# ra8875_40pin_REV-D.net
KiCad netlist of a schematic drawn in EAGLE
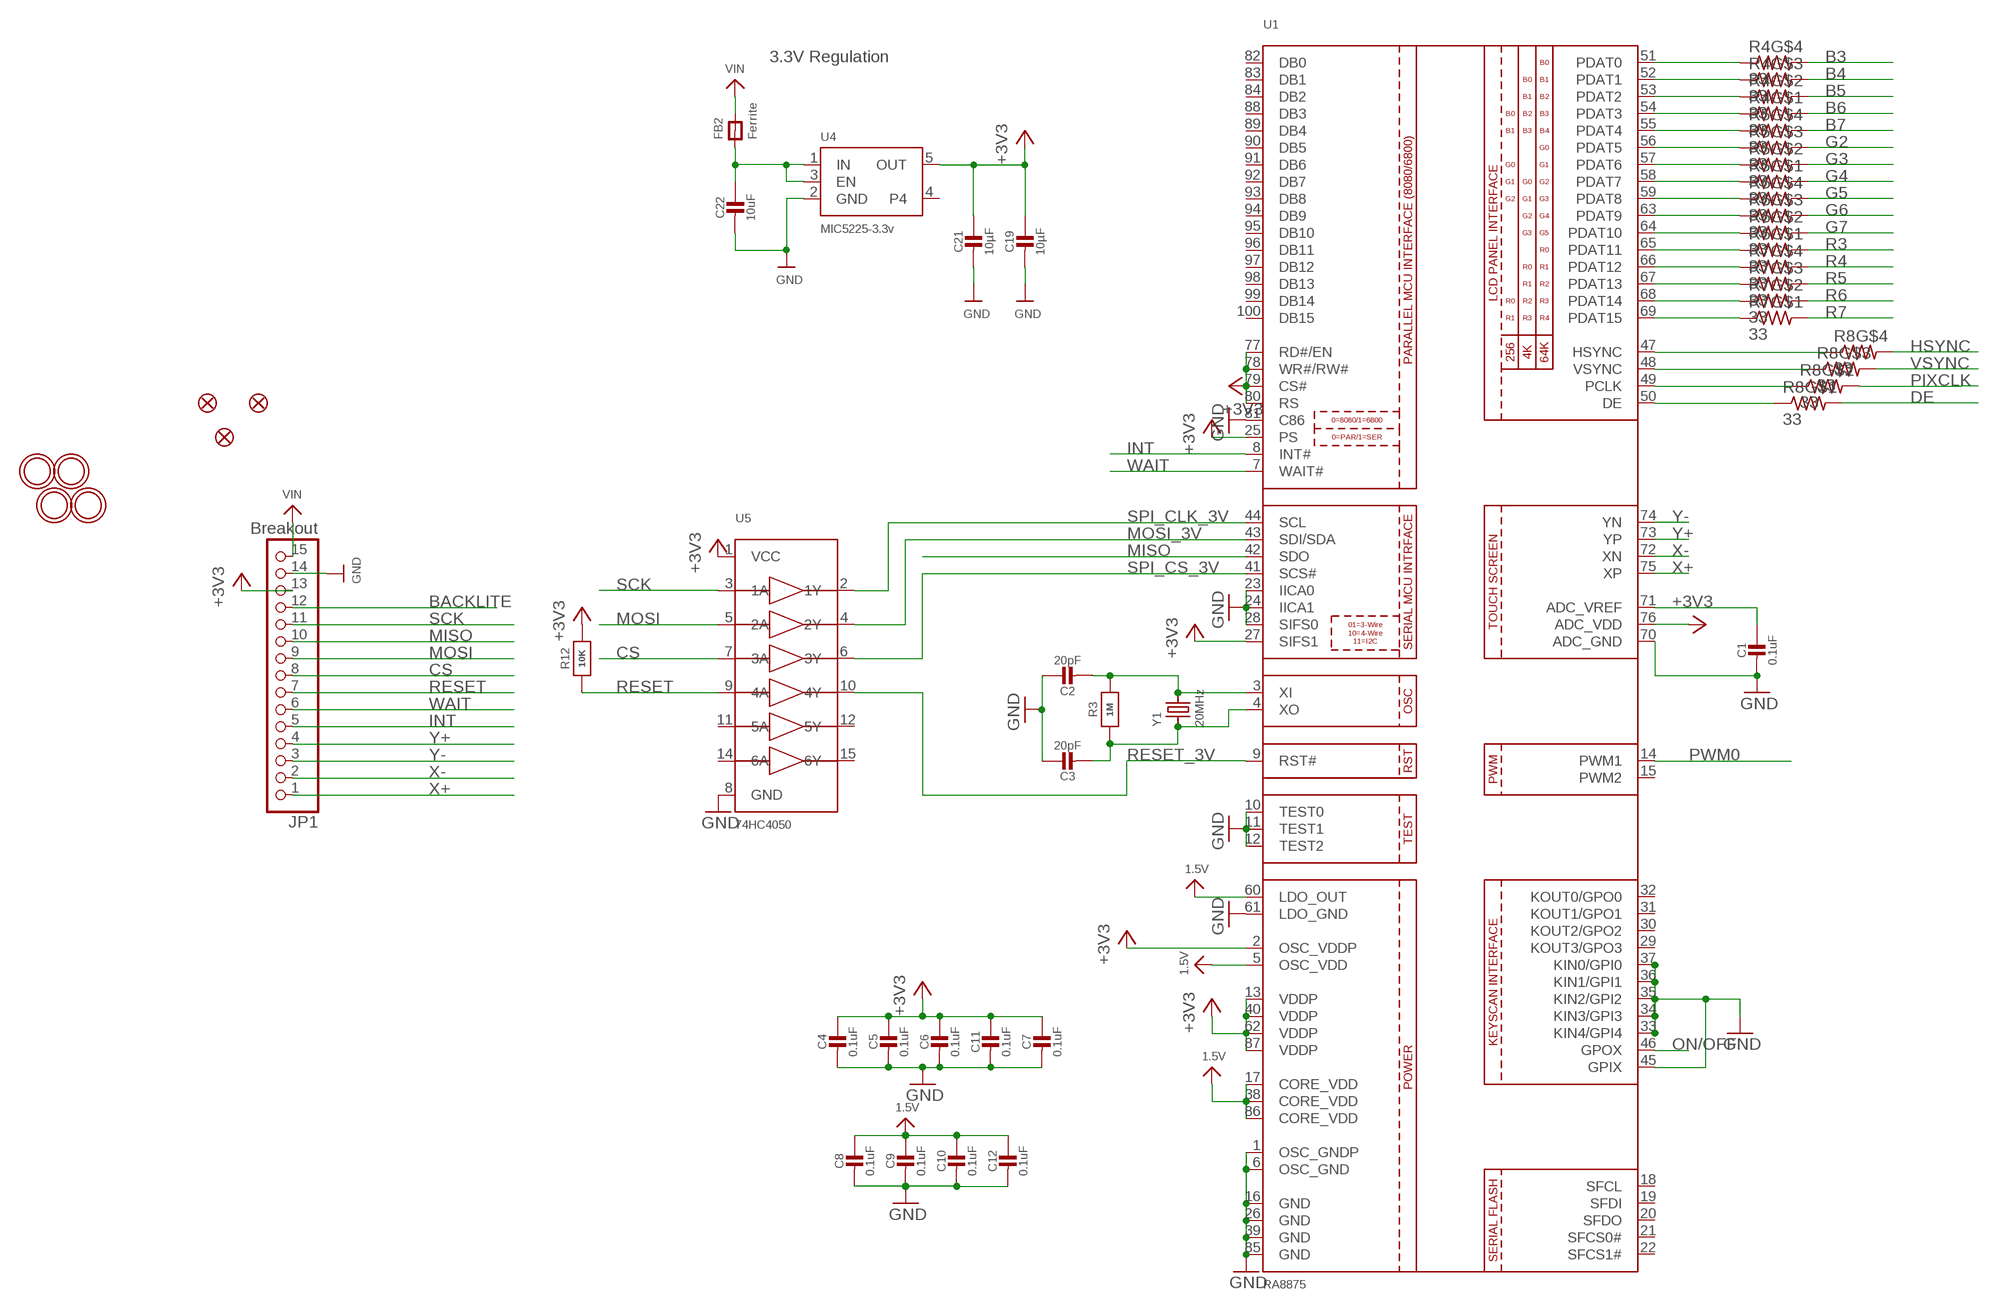
[diagram p0: schematic, sheet 1, part 1 of 2]
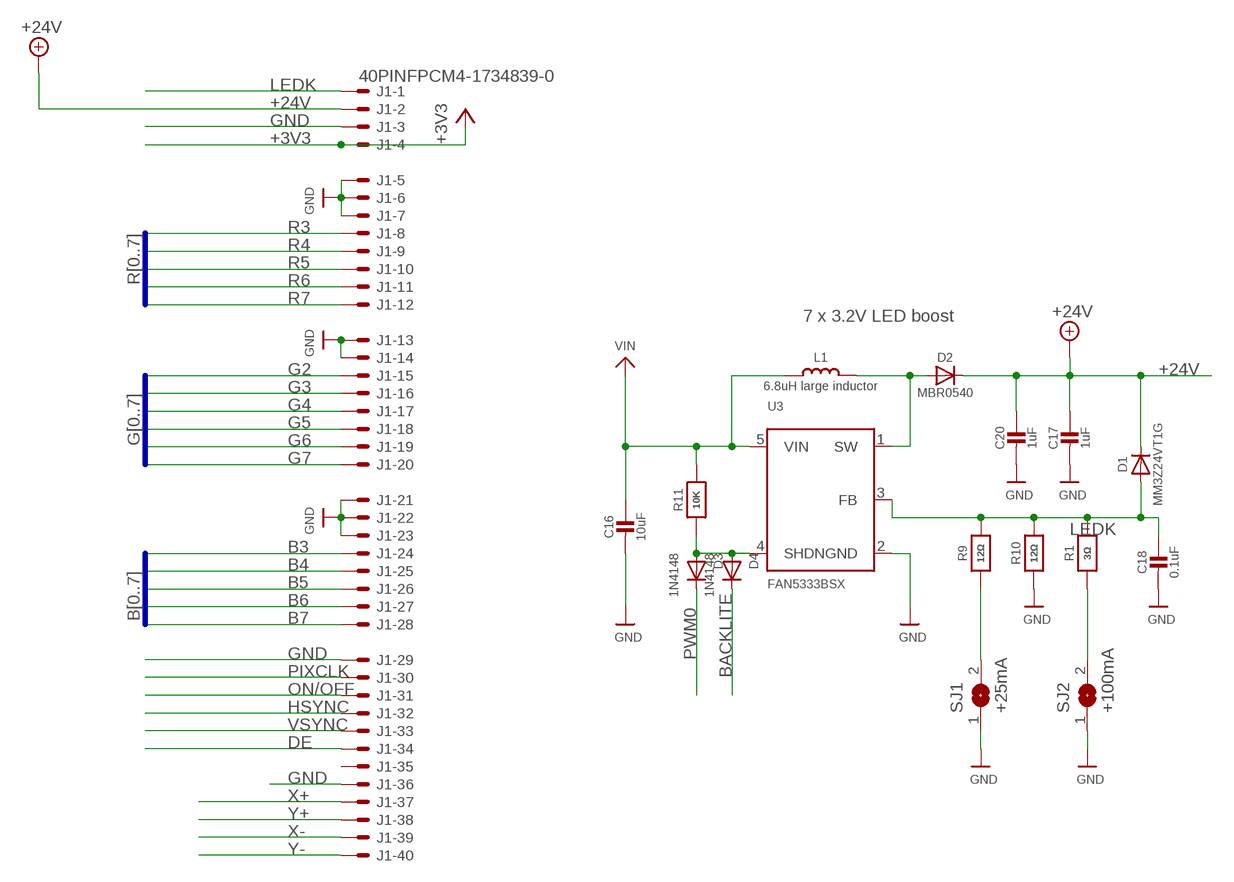
[diagram p1: schematic, sheet 1, part 2 of 2]

(export (version "E")
  (design (tool "Eeschema 10.0.6"))
  (components
    (comp (ref "C1")
      (value "0.1uF")
      (footprint "eagle-import:0805-NO")
      (libsource (lib "eagle-import") (part "CAP_CERAMIC0805-NOOUTLINE"))
    )
    (comp (ref "C2")
      (value "20pF")
      (footprint "eagle-import:0805-NO")
      (libsource (lib "eagle-import") (part "CAP_CERAMIC0805-NOOUTLINE"))
    )
    (comp (ref "C3")
      (value "20pF")
      (footprint "eagle-import:0805-NO")
      (libsource (lib "eagle-import") (part "CAP_CERAMIC0805-NOOUTLINE"))
    )
    (comp (ref "C4")
      (value "0.1uF")
      (footprint "eagle-import:0805-NO")
      (libsource (lib "eagle-import") (part "CAP_CERAMIC0805-NOOUTLINE"))
    )
    (comp (ref "C5")
      (value "0.1uF")
      (footprint "eagle-import:0805-NO")
      (libsource (lib "eagle-import") (part "CAP_CERAMIC0805-NOOUTLINE"))
    )
    (comp (ref "C6")
      (value "0.1uF")
      (footprint "eagle-import:0805-NO")
      (libsource (lib "eagle-import") (part "CAP_CERAMIC0805-NOOUTLINE"))
    )
    (comp (ref "C7")
      (value "0.1uF")
      (footprint "eagle-import:0805-NO")
      (libsource (lib "eagle-import") (part "CAP_CERAMIC0805-NOOUTLINE"))
    )
    (comp (ref "C8")
      (value "0.1uF")
      (footprint "eagle-import:0805-NO")
      (libsource (lib "eagle-import") (part "CAP_CERAMIC0805-NOOUTLINE"))
    )
    (comp (ref "C9")
      (value "0.1uF")
      (footprint "eagle-import:0805-NO")
      (libsource (lib "eagle-import") (part "CAP_CERAMIC0805-NOOUTLINE"))
    )
    (comp (ref "C10")
      (value "0.1uF")
      (footprint "eagle-import:0805-NO")
      (libsource (lib "eagle-import") (part "CAP_CERAMIC0805-NOOUTLINE"))
    )
    (comp (ref "C11")
      (value "0.1uF")
      (footprint "eagle-import:0805-NO")
      (libsource (lib "eagle-import") (part "CAP_CERAMIC0805-NOOUTLINE"))
    )
    (comp (ref "C12")
      (value "0.1uF")
      (footprint "eagle-import:0805-NO")
      (libsource (lib "eagle-import") (part "CAP_CERAMIC0805-NOOUTLINE"))
    )
    (comp (ref "C16")
      (value "10uF")
      (footprint "eagle-import:_0805MP")
      (libsource (lib "eagle-import") (part "CAP_CERAMIC_0805MP"))
    )
    (comp (ref "C17")
      (value "1uF")
      (footprint "eagle-import:_0805MP")
      (libsource (lib "eagle-import") (part "CAP_CERAMIC_0805MP"))
    )
    (comp (ref "C18")
      (value "0.1uF")
      (footprint "eagle-import:_0805MP")
      (libsource (lib "eagle-import") (part "CAP_CERAMIC_0805MP"))
    )
    (comp (ref "C19")
      (value "10µF")
      (footprint "eagle-import:_0805MP")
      (libsource (lib "eagle-import") (part "CAP_CERAMIC_0805MP"))
    )
    (comp (ref "C20")
      (value "1uF")
      (footprint "eagle-import:_0805MP")
      (libsource (lib "eagle-import") (part "CAP_CERAMIC_0805MP"))
    )
    (comp (ref "C21")
      (value "10µF")
      (footprint "eagle-import:_0805MP")
      (libsource (lib "eagle-import") (part "CAP_CERAMIC_0805MP"))
    )
    (comp (ref "C22")
      (value "10uF")
      (footprint "eagle-import:_0805MP")
      (libsource (lib "eagle-import") (part "CAP_CERAMIC_0805MP"))
    )
    (comp (ref "D1")
      (value "MM3Z24VT1G")
      (footprint "eagle-import:SMADIODE")
      (libsource (lib "eagle-import") (part "microbuilder_DIODESMA"))
    )
    (comp (ref "D2")
      (value "MBR0540")
      (footprint "eagle-import:SOD-123")
      (libsource (lib "eagle-import") (part "microbuilder_DIODESOD-123"))
    )
    (comp (ref "D3")
      (value "1N4148")
      (footprint "eagle-import:SOD-323F")
      (libsource (lib "eagle-import") (part "DIODESOD-323F"))
    )
    (comp (ref "D4")
      (value "1N4148")
      (footprint "eagle-import:SOD-323F")
      (libsource (lib "eagle-import") (part "DIODESOD-323F"))
    )
    (comp (ref "FB2")
      (value "Ferrite")
      (footprint "eagle-import:_0805MP")
      (libsource (lib "eagle-import") (part "FERRITE_0805MP"))
    )
    (comp (ref "FID1")
      (value "FIDUCIAL\"\"")
      (footprint "eagle-import:FIDUCIAL_1MM")
      (libsource (lib "eagle-import") (part "FIDUCIAL{dblquote}{dblquote}"))
    )
    (comp (ref "FID2")
      (value "FIDUCIAL\"\"")
      (footprint "eagle-import:FIDUCIAL_1MM")
      (libsource (lib "eagle-import") (part "FIDUCIAL{dblquote}{dblquote}"))
    )
    (comp (ref "FID3")
      (value "FIDUCIAL\"\"")
      (footprint "eagle-import:FIDUCIAL_1MM")
      (libsource (lib "eagle-import") (part "FIDUCIAL{dblquote}{dblquote}"))
    )
    (comp (ref "J1")
      (value "40PINFPCM4-1734839-0")
      (footprint "eagle-import:4-1734839-0")
      (libsource (lib "eagle-import") (part "40PINFPC4-1734839-0M"))
    )
    (comp (ref "JP1")
      (value "Breakout")
      (footprint "eagle-import:1X15-CB")
      (libsource (lib "eagle-import") (part "PINHD-1X15-CB"))
    )
    (comp (ref "L1")
      (value "6.8uH large inductor")
      (footprint "eagle-import:INDUCTOR_5X5MM_NR5040_NOTHERMALS")
      (libsource (lib "eagle-import") (part "INDUCTORNR5040"))
    )
    (comp (ref "R1")
      (value "3Ω")
      (footprint "eagle-import:_0805MP")
      (libsource (lib "eagle-import") (part "RESISTOR_0805MP"))
    )
    (comp (ref "R3")
      (value "1M")
      (footprint "eagle-import:0805-NO")
      (libsource (lib "eagle-import") (part "RESISTOR0805_NOOUTLINE"))
    )
    (comp (ref "R4")
      (value "33")
      (footprint "eagle-import:RESPACK_4X0603")
      (libsource (lib "eagle-import") (part "RESISTOR_4PACK_US"))
    )
    (comp (ref "R5")
      (value "33")
      (footprint "eagle-import:RESPACK_4X0603")
      (libsource (lib "eagle-import") (part "RESISTOR_4PACK_US"))
    )
    (comp (ref "R6")
      (value "33")
      (footprint "eagle-import:RESPACK_4X0603")
      (libsource (lib "eagle-import") (part "RESISTOR_4PACK_US"))
    )
    (comp (ref "R7")
      (value "33")
      (footprint "eagle-import:RESPACK_4X0603")
      (libsource (lib "eagle-import") (part "RESISTOR_4PACK_US"))
    )
    (comp (ref "R8")
      (value "33")
      (footprint "eagle-import:RESPACK_4X0603")
      (libsource (lib "eagle-import") (part "RESISTOR_4PACK_US"))
    )
    (comp (ref "R9")
      (value "12Ω")
      (footprint "eagle-import:_0805MP")
      (libsource (lib "eagle-import") (part "RESISTOR_0805MP"))
    )
    (comp (ref "R10")
      (value "12Ω")
      (footprint "eagle-import:_0805MP")
      (libsource (lib "eagle-import") (part "RESISTOR_0805MP"))
    )
    (comp (ref "R11")
      (value "10K")
      (footprint "eagle-import:_0805MP")
      (libsource (lib "eagle-import") (part "RESISTOR_0805MP"))
    )
    (comp (ref "R12")
      (value "10K")
      (footprint "eagle-import:0805-NO")
      (libsource (lib "eagle-import") (part "RESISTOR0805_NOOUTLINE"))
    )
    (comp (ref "SJ1")
      (value "+25mA")
      (footprint "eagle-import:SOLDERJUMPER_ARROW_NOPASTE")
      (libsource (lib "eagle-import") (part "SOLDERJUMPER"))
    )
    (comp (ref "SJ2")
      (value "+100mA")
      (footprint "eagle-import:SOLDERJUMPER_ARROW_NOPASTE")
      (fields (field (name "BOM") "EXCLUDE"))
      (libsource (lib "eagle-import") (part "SOLDERJUMPER"))
    )
    (comp (ref "U$21")
      (value "MOUNTINGHOLE2.5")
      (footprint "eagle-import:MOUNTINGHOLE_2.5_PLATED")
      (libsource (lib "eagle-import") (part "MOUNTINGHOLE2.5"))
    )
    (comp (ref "U$22")
      (value "MOUNTINGHOLE2.5")
      (footprint "eagle-import:MOUNTINGHOLE_2.5_PLATED")
      (libsource (lib "eagle-import") (part "MOUNTINGHOLE2.5"))
    )
    (comp (ref "U$23")
      (value "MOUNTINGHOLE2.5")
      (footprint "eagle-import:MOUNTINGHOLE_2.5_PLATED")
      (libsource (lib "eagle-import") (part "MOUNTINGHOLE2.5"))
    )
    (comp (ref "U$24")
      (value "MOUNTINGHOLE2.5")
      (footprint "eagle-import:MOUNTINGHOLE_2.5_PLATED")
      (libsource (lib "eagle-import") (part "MOUNTINGHOLE2.5"))
    )
    (comp (ref "U1")
      (value "RA8875")
      (footprint "eagle-import:LQFP100")
      (libsource (lib "eagle-import") (part "RA8875"))
    )
    (comp (ref "U3")
      (value "FAN5333BSX")
      (footprint "eagle-import:SOT23-5@1")
      (libsource (lib "eagle-import") (part "FAN5331"))
    )
    (comp (ref "U4")
      (value "MIC5225-3.3v")
      (footprint "eagle-import:SOT23-5")
      (libsource (lib "eagle-import") (part "VREG_SOT23-5"))
    )
    (comp (ref "U5")
      (value "74HC4050")
      (footprint "eagle-import:SOIC16")
      (libsource (lib "eagle-import") (part "74HC4050D"))
    )
    (comp (ref "Y1")
      (value "20MHz")
      (footprint "eagle-import:CRYSTAL_3.2X2.5")
      (libsource (lib "eagle-import") (part "CRYSTAL3.2X2.5"))
    )
  )
  (nets
    (net (code "9") (name "+3V3") (class "Default")
      (node (ref "C11") (pin "1") (pinfunction "1_1") (pintype "passive"))
      (node (ref "C19") (pin "1") (pinfunction "1_1") (pintype "passive"))
      (node (ref "C21") (pin "1") (pinfunction "1_1") (pintype "passive"))
      (node (ref "C4") (pin "1") (pinfunction "1_1") (pintype "passive"))
      (node (ref "C5") (pin "1") (pinfunction "1_1") (pintype "passive"))
      (node (ref "C6") (pin "1") (pinfunction "1_1") (pintype "passive"))
      (node (ref "C7") (pin "1") (pinfunction "1_1") (pintype "passive"))
      (node (ref "J1") (pin "4") (pinfunction "MS_4") (pintype "passive"))
      (node (ref "JP1") (pin "13") (pinfunction "13_13") (pintype "passive"))
      (node (ref "R12") (pin "2") (pinfunction "2_2") (pintype "passive"))
      (node (ref "U1") (pin "13") (pinfunction "VDDP_13") (pintype "power_in"))
      (node (ref "U1") (pin "2") (pinfunction "OSC_VDDP_2") (pintype "power_in"))
      (node (ref "U1") (pin "25") (pinfunction "PS_25") (pintype "input"))
      (node (ref "U1") (pin "27") (pinfunction "SIFS1_27") (pintype "input"))
      (node (ref "U1") (pin "40") (pinfunction "VDDP_40") (pintype "power_in"))
      (node (ref "U1") (pin "62") (pinfunction "VDDP_62") (pintype "power_in"))
      (node (ref "U1") (pin "76") (pinfunction "ADC_VDD_76") (pintype "power_in"))
      (node (ref "U1") (pin "77") (pinfunction "RD#/EN_77") (pintype "input"))
      (node (ref "U1") (pin "78") (pinfunction "WR#/RW#_78") (pintype "input"))
      (node (ref "U1") (pin "79") (pinfunction "CS#_79") (pintype "input"))
      (node (ref "U1") (pin "80") (pinfunction "RS_80") (pintype "input"))
      (node (ref "U1") (pin "87") (pinfunction "VDDP_87") (pintype "power_in"))
      (node (ref "U4") (pin "5") (pinfunction "OUT_5") (pintype "power_in"))
      (node (ref "U5") (pin "1") (pinfunction "VCC_1") (pintype "bidirectional"))
    )
    (net (code "10") (name "+24V") (class "Default")
      (node (ref "C17") (pin "1") (pinfunction "1_1") (pintype "passive"))
      (node (ref "C20") (pin "1") (pinfunction "1_1") (pintype "passive"))
      (node (ref "D1") (pin "C") (pinfunction "C_C") (pintype "passive"))
      (node (ref "D2") (pin "C") (pinfunction "C_C") (pintype "passive"))
      (node (ref "J1") (pin "2") (pinfunction "MS_2") (pintype "passive"))
    )
    (net (code "11") (name "/B3") (class "Default")
      (node (ref "J1") (pin "24") (pinfunction "MS_24") (pintype "passive"))
      (node (ref "R4") (pin "5") (pinfunction "2_5") (pintype "passive"))
    )
    (net (code "12") (name "/B4") (class "Default")
      (node (ref "J1") (pin "25") (pinfunction "MS_25") (pintype "passive"))
      (node (ref "R4") (pin "6") (pinfunction "2_6") (pintype "passive"))
    )
    (net (code "13") (name "/B5") (class "Default")
      (node (ref "J1") (pin "26") (pinfunction "MS_26") (pintype "passive"))
      (node (ref "R4") (pin "7") (pinfunction "2_7") (pintype "passive"))
    )
    (net (code "14") (name "/B6") (class "Default")
      (node (ref "J1") (pin "27") (pinfunction "MS_27") (pintype "passive"))
      (node (ref "R4") (pin "8") (pinfunction "2_8") (pintype "passive"))
    )
    (net (code "15") (name "/B7") (class "Default")
      (node (ref "J1") (pin "28") (pinfunction "MS_28") (pintype "passive"))
      (node (ref "R5") (pin "5") (pinfunction "2_5") (pintype "passive"))
    )
    (net (code "16") (name "/BACKLITE") (class "Default")
      (node (ref "D4") (pin "C") (pinfunction "C_C") (pintype "passive"))
      (node (ref "JP1") (pin "12") (pinfunction "12_12") (pintype "passive"))
    )
    (net (code "18") (name "/CS") (class "Default")
      (node (ref "JP1") (pin "8") (pinfunction "8_8") (pintype "passive"))
      (node (ref "U5") (pin "7") (pinfunction "3A_7") (pintype "bidirectional"))
    )
    (net (code "19") (name "/DE") (class "Default")
      (node (ref "J1") (pin "34") (pinfunction "MS_34") (pintype "passive"))
      (node (ref "R8") (pin "8") (pinfunction "2_8") (pintype "passive"))
    )
    (net (code "20") (name "/G2") (class "Default")
      (node (ref "J1") (pin "15") (pinfunction "MS_15") (pintype "passive"))
      (node (ref "R5") (pin "6") (pinfunction "2_6") (pintype "passive"))
    )
    (net (code "21") (name "/G3") (class "Default")
      (node (ref "J1") (pin "16") (pinfunction "MS_16") (pintype "passive"))
      (node (ref "R5") (pin "7") (pinfunction "2_7") (pintype "passive"))
    )
    (net (code "22") (name "/G4") (class "Default")
      (node (ref "J1") (pin "17") (pinfunction "MS_17") (pintype "passive"))
      (node (ref "R5") (pin "8") (pinfunction "2_8") (pintype "passive"))
    )
    (net (code "23") (name "/G5") (class "Default")
      (node (ref "J1") (pin "18") (pinfunction "MS_18") (pintype "passive"))
      (node (ref "R6") (pin "5") (pinfunction "2_5") (pintype "passive"))
    )
    (net (code "24") (name "/G6") (class "Default")
      (node (ref "J1") (pin "19") (pinfunction "MS_19") (pintype "passive"))
      (node (ref "R6") (pin "6") (pinfunction "2_6") (pintype "passive"))
    )
    (net (code "25") (name "/G7") (class "Default")
      (node (ref "J1") (pin "20") (pinfunction "MS_20") (pintype "passive"))
      (node (ref "R6") (pin "7") (pinfunction "2_7") (pintype "passive"))
    )
    (net (code "27") (name "/HSYNC") (class "Default")
      (node (ref "J1") (pin "32") (pinfunction "MS_32") (pintype "passive"))
      (node (ref "R8") (pin "5") (pinfunction "2_5") (pintype "passive"))
    )
    (net (code "28") (name "/INT") (class "Default")
      (node (ref "JP1") (pin "5") (pinfunction "5_5") (pintype "passive"))
      (node (ref "U1") (pin "8") (pinfunction "INT#_8") (pintype "output"))
    )
    (net (code "29") (name "/LEDK") (class "Default")
      (node (ref "C18") (pin "1") (pinfunction "1_1") (pintype "passive"))
      (node (ref "D1") (pin "A") (pinfunction "A_A") (pintype "passive"))
      (node (ref "J1") (pin "1") (pinfunction "MSV_1") (pintype "passive"))
      (node (ref "R1") (pin "2") (pinfunction "2_2") (pintype "passive"))
      (node (ref "R10") (pin "2") (pinfunction "2_2") (pintype "passive"))
      (node (ref "R9") (pin "2") (pinfunction "2_2") (pintype "passive"))
      (node (ref "U3") (pin "3") (pinfunction "FB_3") (pintype "bidirectional"))
    )
    (net (code "30") (name "/MISO") (class "Default")
      (node (ref "JP1") (pin "10") (pinfunction "10_10") (pintype "passive"))
      (node (ref "U1") (pin "42") (pinfunction "SDO_42") (pintype "output"))
    )
    (net (code "31") (name "/MOSI") (class "Default")
      (node (ref "JP1") (pin "9") (pinfunction "9_9") (pintype "passive"))
      (node (ref "U5") (pin "5") (pinfunction "2A_5") (pintype "bidirectional"))
    )
    (net (code "32") (name "/MOSI_3V") (class "Default")
      (node (ref "U1") (pin "43") (pinfunction "SDI/SDA_43") (pintype "bidirectional"))
      (node (ref "U5") (pin "4") (pinfunction "2Y_4") (pintype "bidirectional"))
    )
    (net (code "33") (name "/ON{slash}OFF") (class "Default")
      (node (ref "J1") (pin "31") (pinfunction "MS_31") (pintype "passive"))
      (node (ref "U1") (pin "46") (pinfunction "GPOX_46") (pintype "output"))
    )
    (net (code "34") (name "/PIXCLK") (class "Default")
      (node (ref "J1") (pin "30") (pinfunction "MS_30") (pintype "passive"))
      (node (ref "R8") (pin "7") (pinfunction "2_7") (pintype "passive"))
    )
    (net (code "35") (name "/PWM0") (class "Default")
      (node (ref "D3") (pin "C") (pinfunction "C_C") (pintype "passive"))
      (node (ref "U1") (pin "14") (pinfunction "PWM1_14") (pintype "output"))
    )
    (net (code "36") (name "/R3") (class "Default")
      (node (ref "J1") (pin "8") (pinfunction "MS_8") (pintype "passive"))
      (node (ref "R6") (pin "8") (pinfunction "2_8") (pintype "passive"))
    )
    (net (code "37") (name "/R4") (class "Default")
      (node (ref "J1") (pin "9") (pinfunction "MS_9") (pintype "passive"))
      (node (ref "R7") (pin "5") (pinfunction "2_5") (pintype "passive"))
    )
    (net (code "38") (name "/R5") (class "Default")
      (node (ref "J1") (pin "10") (pinfunction "MS_10") (pintype "passive"))
      (node (ref "R7") (pin "6") (pinfunction "2_6") (pintype "passive"))
    )
    (net (code "39") (name "/R6") (class "Default")
      (node (ref "J1") (pin "11") (pinfunction "MS_11") (pintype "passive"))
      (node (ref "R7") (pin "7") (pinfunction "2_7") (pintype "passive"))
    )
    (net (code "40") (name "/R7") (class "Default")
      (node (ref "J1") (pin "12") (pinfunction "MS_12") (pintype "passive"))
      (node (ref "R7") (pin "8") (pinfunction "2_8") (pintype "passive"))
    )
    (net (code "41") (name "/RESET") (class "Default")
      (node (ref "JP1") (pin "7") (pinfunction "7_7") (pintype "passive"))
      (node (ref "R12") (pin "1") (pinfunction "1_1") (pintype "passive"))
      (node (ref "U5") (pin "9") (pinfunction "4A_9") (pintype "bidirectional"))
    )
    (net (code "42") (name "/RESET_3V") (class "Default")
      (node (ref "U1") (pin "9") (pinfunction "RST#_9") (pintype "input"))
      (node (ref "U5") (pin "10") (pinfunction "4Y_10") (pintype "bidirectional"))
    )
    (net (code "44") (name "/SCK") (class "Default")
      (node (ref "JP1") (pin "11") (pinfunction "11_11") (pintype "passive"))
      (node (ref "U5") (pin "3") (pinfunction "1A_3") (pintype "bidirectional"))
    )
    (net (code "45") (name "/SPI_CLK_3V") (class "Default")
      (node (ref "U1") (pin "44") (pinfunction "SCL_44") (pintype "output"))
      (node (ref "U5") (pin "2") (pinfunction "1Y_2") (pintype "bidirectional"))
    )
    (net (code "46") (name "/SPI_CS_3V") (class "Default")
      (node (ref "U1") (pin "41") (pinfunction "SCS#_41") (pintype "output"))
      (node (ref "U5") (pin "6") (pinfunction "3Y_6") (pintype "bidirectional"))
    )
    (net (code "47") (name "/VSYNC") (class "Default")
      (node (ref "J1") (pin "33") (pinfunction "MS_33") (pintype "passive"))
      (node (ref "R8") (pin "6") (pinfunction "2_6") (pintype "passive"))
    )
    (net (code "48") (name "/WAIT") (class "Default")
      (node (ref "JP1") (pin "6") (pinfunction "6_6") (pintype "passive"))
      (node (ref "U1") (pin "7") (pinfunction "WAIT#_7") (pintype "output"))
    )
    (net (code "49") (name "/X+") (class "Default")
      (node (ref "J1") (pin "37") (pinfunction "MS_37") (pintype "passive"))
      (node (ref "JP1") (pin "1") (pinfunction "1_1") (pintype "passive"))
      (node (ref "U1") (pin "75") (pinfunction "XP_75") (pintype "bidirectional"))
    )
    (net (code "50") (name "/X-") (class "Default")
      (node (ref "J1") (pin "39") (pinfunction "MS_39") (pintype "passive"))
      (node (ref "JP1") (pin "2") (pinfunction "2_2") (pintype "passive"))
      (node (ref "U1") (pin "72") (pinfunction "XN_72") (pintype "bidirectional"))
    )
    (net (code "51") (name "/Y+") (class "Default")
      (node (ref "J1") (pin "38") (pinfunction "MS_38") (pintype "passive"))
      (node (ref "JP1") (pin "4") (pinfunction "4_4") (pintype "passive"))
      (node (ref "U1") (pin "73") (pinfunction "YP_73") (pintype "bidirectional"))
    )
    (net (code "52") (name "/Y-") (class "Default")
      (node (ref "J1") (pin "40") (pinfunction "MS_40") (pintype "passive"))
      (node (ref "JP1") (pin "3") (pinfunction "3_3") (pintype "passive"))
      (node (ref "U1") (pin "74") (pinfunction "YN_74") (pintype "bidirectional"))
    )
    (net (code "53") (name "1.5V") (class "Default")
      (node (ref "C10") (pin "1") (pinfunction "1_1") (pintype "passive"))
      (node (ref "C12") (pin "1") (pinfunction "1_1") (pintype "passive"))
      (node (ref "C8") (pin "1") (pinfunction "1_1") (pintype "passive"))
      (node (ref "C9") (pin "1") (pinfunction "1_1") (pintype "passive"))
      (node (ref "U1") (pin "17") (pinfunction "CORE_VDD_17") (pintype "power_in"))
      (node (ref "U1") (pin "38") (pinfunction "CORE_VDD_38") (pintype "power_in"))
      (node (ref "U1") (pin "5") (pinfunction "OSC_VDD_5") (pintype "power_in"))
      (node (ref "U1") (pin "60") (pinfunction "LDO_OUT_60") (pintype "power_in"))
      (node (ref "U1") (pin "86") (pinfunction "CORE_VDD_86") (pintype "power_in"))
    )
    (net (code "54") (name "GND") (class "Default")
      (node (ref "C1") (pin "2") (pinfunction "2_2") (pintype "passive"))
      (node (ref "C10") (pin "2") (pinfunction "2_2") (pintype "passive"))
      (node (ref "C11") (pin "2") (pinfunction "2_2") (pintype "passive"))
      (node (ref "C12") (pin "2") (pinfunction "2_2") (pintype "passive"))
      (node (ref "C16") (pin "2") (pinfunction "2_2") (pintype "passive"))
      (node (ref "C17") (pin "2") (pinfunction "2_2") (pintype "passive"))
      (node (ref "C18") (pin "2") (pinfunction "2_2") (pintype "passive"))
      (node (ref "C19") (pin "2") (pinfunction "2_2") (pintype "passive"))
      (node (ref "C2") (pin "1") (pinfunction "1_1") (pintype "passive"))
      (node (ref "C20") (pin "2") (pinfunction "2_2") (pintype "passive"))
      (node (ref "C21") (pin "2") (pinfunction "2_2") (pintype "passive"))
      (node (ref "C22") (pin "2") (pinfunction "2_2") (pintype "passive"))
      (node (ref "C3") (pin "1") (pinfunction "1_1") (pintype "passive"))
      (node (ref "C4") (pin "2") (pinfunction "2_2") (pintype "passive"))
      (node (ref "C5") (pin "2") (pinfunction "2_2") (pintype "passive"))
      (node (ref "C6") (pin "2") (pinfunction "2_2") (pintype "passive"))
      (node (ref "C7") (pin "2") (pinfunction "2_2") (pintype "passive"))
      (node (ref "C8") (pin "2") (pinfunction "2_2") (pintype "passive"))
      (node (ref "C9") (pin "2") (pinfunction "2_2") (pintype "passive"))
      (node (ref "J1") (pin "13") (pinfunction "MS_13") (pintype "passive"))
      (node (ref "J1") (pin "14") (pinfunction "MS_14") (pintype "passive"))
      (node (ref "J1") (pin "21") (pinfunction "MS_21") (pintype "passive"))
      (node (ref "J1") (pin "22") (pinfunction "MS_22") (pintype "passive"))
      (node (ref "J1") (pin "23") (pinfunction "MS_23") (pintype "passive"))
      (node (ref "J1") (pin "29") (pinfunction "MS_29") (pintype "passive"))
      (node (ref "J1") (pin "3") (pinfunction "MS_3") (pintype "passive"))
      (node (ref "J1") (pin "36") (pinfunction "MS_36") (pintype "passive"))
      (node (ref "J1") (pin "5") (pinfunction "MS_5") (pintype "passive"))
      (node (ref "J1") (pin "6") (pinfunction "MS_6") (pintype "passive"))
      (node (ref "J1") (pin "7") (pinfunction "MS_7") (pintype "passive"))
      (node (ref "JP1") (pin "14") (pinfunction "14_14") (pintype "passive"))
      (node (ref "R10") (pin "1") (pinfunction "1_1") (pintype "passive"))
      (node (ref "SJ1") (pin "1") (pinfunction "1_1") (pintype "passive"))
      (node (ref "SJ2") (pin "1") (pinfunction "1_1") (pintype "passive"))
      (node (ref "U1") (pin "1") (pinfunction "OSC_GNDP_1") (pintype "power_in"))
      (node (ref "U1") (pin "10") (pinfunction "TEST0_10") (pintype "input"))
      (node (ref "U1") (pin "11") (pinfunction "TEST1_11") (pintype "input"))
      (node (ref "U1") (pin "12") (pinfunction "TEST2_12") (pintype "input"))
      (node (ref "U1") (pin "16") (pinfunction "GND_16") (pintype "power_in"))
      (node (ref "U1") (pin "23") (pinfunction "IICA0_23") (pintype "input"))
      (node (ref "U1") (pin "24") (pinfunction "IICA1_24") (pintype "input"))
      (node (ref "U1") (pin "26") (pinfunction "GND_26") (pintype "power_in"))
      (node (ref "U1") (pin "28") (pinfunction "SIFS0_28") (pintype "input"))
      (node (ref "U1") (pin "33") (pinfunction "KIN4/GPI4_33") (pintype "input"))
      (node (ref "U1") (pin "34") (pinfunction "KIN3/GPI3_34") (pintype "input"))
      (node (ref "U1") (pin "35") (pinfunction "KIN2/GPI2_35") (pintype "input"))
      (node (ref "U1") (pin "36") (pinfunction "KIN1/GPI1_36") (pintype "input"))
      (node (ref "U1") (pin "37") (pinfunction "KIN0/GPI0_37") (pintype "input"))
      (node (ref "U1") (pin "39") (pinfunction "GND_39") (pintype "power_in"))
      (node (ref "U1") (pin "45") (pinfunction "GPIX_45") (pintype "input"))
      (node (ref "U1") (pin "6") (pinfunction "OSC_GND_6") (pintype "power_in"))
      (node (ref "U1") (pin "61") (pinfunction "LDO_GND_61") (pintype "power_in"))
      (node (ref "U1") (pin "70") (pinfunction "ADC_GND_70") (pintype "power_in"))
      (node (ref "U1") (pin "81") (pinfunction "C86_81") (pintype "input"))
      (node (ref "U1") (pin "85") (pinfunction "GND_85") (pintype "power_in"))
      (node (ref "U3") (pin "2") (pinfunction "GND_2") (pintype "bidirectional"))
      (node (ref "U4") (pin "2") (pinfunction "GND_2") (pintype "power_in"))
      (node (ref "U5") (pin "8") (pinfunction "GND_8") (pintype "bidirectional"))
    )
    (net (code "55") (name "Net-(FB2-P$1)") (class "Default")
      (node (ref "C22") (pin "1") (pinfunction "1_1") (pintype "passive"))
      (node (ref "FB2") (pin "1") (pinfunction "P$1_1") (pintype "passive"))
      (node (ref "U4") (pin "1") (pinfunction "IN_1") (pintype "power_in"))
      (node (ref "U4") (pin "3") (pinfunction "EN_3") (pintype "input"))
    )
    (net (code "56") (name "Net-(L1-2)") (class "Default")
      (node (ref "D2") (pin "A") (pinfunction "A_A") (pintype "passive"))
      (node (ref "L1") (pin "P$2") (pinfunction "2_P$2") (pintype "passive"))
      (node (ref "U3") (pin "1") (pinfunction "SW_1") (pintype "bidirectional"))
    )
    (net (code "57") (name "Net-(R1-Pad1)") (class "Default")
      (node (ref "R1") (pin "1") (pinfunction "1_1") (pintype "passive"))
      (node (ref "SJ2") (pin "2") (pinfunction "2_2") (pintype "passive"))
    )
    (net (code "58") (name "Net-(R4B-1)") (class "Default")
      (node (ref "R4") (pin "2") (pinfunction "1_2") (pintype "passive"))
      (node (ref "U1") (pin "53") (pinfunction "PDAT2_53") (pintype "output"))
    )
    (net (code "59") (name "Net-(R4C-1)") (class "Default")
      (node (ref "R4") (pin "3") (pinfunction "1_3") (pintype "passive"))
      (node (ref "U1") (pin "52") (pinfunction "PDAT1_52") (pintype "output"))
    )
    (net (code "60") (name "Net-(R4D-1)") (class "Default")
      (node (ref "R4") (pin "4") (pinfunction "1_4") (pintype "passive"))
      (node (ref "U1") (pin "51") (pinfunction "PDAT0_51") (pintype "output"))
    )
    (net (code "61") (name "Net-(R5B-1)") (class "Default")
      (node (ref "R5") (pin "2") (pinfunction "1_2") (pintype "passive"))
      (node (ref "U1") (pin "57") (pinfunction "PDAT6_57") (pintype "output"))
    )
    (net (code "62") (name "Net-(R5C-1)") (class "Default")
      (node (ref "R5") (pin "3") (pinfunction "1_3") (pintype "passive"))
      (node (ref "U1") (pin "56") (pinfunction "PDAT5_56") (pintype "output"))
    )
    (net (code "63") (name "Net-(R5D-1)") (class "Default")
      (node (ref "R5") (pin "4") (pinfunction "1_4") (pintype "passive"))
      (node (ref "U1") (pin "55") (pinfunction "PDAT4_55") (pintype "output"))
    )
    (net (code "64") (name "Net-(R6B-1)") (class "Default")
      (node (ref "R6") (pin "2") (pinfunction "1_2") (pintype "passive"))
      (node (ref "U1") (pin "64") (pinfunction "PDAT10_64") (pintype "output"))
    )
    (net (code "65") (name "Net-(R6C-1)") (class "Default")
      (node (ref "R6") (pin "3") (pinfunction "1_3") (pintype "passive"))
      (node (ref "U1") (pin "63") (pinfunction "PDAT9_63") (pintype "output"))
    )
    (net (code "66") (name "Net-(R6D-1)") (class "Default")
      (node (ref "R6") (pin "4") (pinfunction "1_4") (pintype "passive"))
      (node (ref "U1") (pin "59") (pinfunction "PDAT8_59") (pintype "output"))
    )
    (net (code "67") (name "Net-(R7B-1)") (class "Default")
      (node (ref "R7") (pin "2") (pinfunction "1_2") (pintype "passive"))
      (node (ref "U1") (pin "68") (pinfunction "PDAT14_68") (pintype "output"))
    )
    (net (code "68") (name "Net-(R7C-1)") (class "Default")
      (node (ref "R7") (pin "3") (pinfunction "1_3") (pintype "passive"))
      (node (ref "U1") (pin "67") (pinfunction "PDAT13_67") (pintype "output"))
    )
    (net (code "69") (name "Net-(R7D-1)") (class "Default")
      (node (ref "R7") (pin "4") (pinfunction "1_4") (pintype "passive"))
      (node (ref "U1") (pin "66") (pinfunction "PDAT12_66") (pintype "output"))
    )
    (net (code "70") (name "Net-(R8B-1)") (class "Default")
      (node (ref "R8") (pin "2") (pinfunction "1_2") (pintype "passive"))
      (node (ref "U1") (pin "49") (pinfunction "PCLK_49") (pintype "output"))
    )
    (net (code "71") (name "Net-(R8C-1)") (class "Default")
      (node (ref "R8") (pin "3") (pinfunction "1_3") (pintype "passive"))
      (node (ref "U1") (pin "48") (pinfunction "VSYNC_48") (pintype "output"))
    )
    (net (code "72") (name "Net-(R8D-1)") (class "Default")
      (node (ref "R8") (pin "4") (pinfunction "1_4") (pintype "passive"))
      (node (ref "U1") (pin "47") (pinfunction "HSYNC_47") (pintype "output"))
    )
    (net (code "73") (name "Net-(R9-Pad1)") (class "Default")
      (node (ref "R9") (pin "1") (pinfunction "1_1") (pintype "passive"))
      (node (ref "SJ1") (pin "2") (pinfunction "2_2") (pintype "passive"))
    )
    (net (code "74") (name "Net-(U1-ADC_VREF)") (class "Default")
      (node (ref "C1") (pin "1") (pinfunction "1_1") (pintype "passive"))
      (node (ref "U1") (pin "71") (pinfunction "ADC_VREF_71") (pintype "input"))
    )
    (net (code "75") (name "Net-(U1-DE)") (class "Default")
      (node (ref "R8") (pin "1") (pinfunction "1_1") (pintype "passive"))
      (node (ref "U1") (pin "50") (pinfunction "DE_50") (pintype "output"))
    )
    (net (code "76") (name "Net-(U1-PDAT3)") (class "Default")
      (node (ref "R4") (pin "1") (pinfunction "1_1") (pintype "passive"))
      (node (ref "U1") (pin "54") (pinfunction "PDAT3_54") (pintype "output"))
    )
    (net (code "77") (name "Net-(U1-PDAT7)") (class "Default")
      (node (ref "R5") (pin "1") (pinfunction "1_1") (pintype "passive"))
      (node (ref "U1") (pin "58") (pinfunction "PDAT7_58") (pintype "output"))
    )
    (net (code "78") (name "Net-(U1-PDAT11)") (class "Default")
      (node (ref "R6") (pin "1") (pinfunction "1_1") (pintype "passive"))
      (node (ref "U1") (pin "65") (pinfunction "PDAT11_65") (pintype "output"))
    )
    (net (code "79") (name "Net-(U1-PDAT15)") (class "Default")
      (node (ref "R7") (pin "1") (pinfunction "1_1") (pintype "passive"))
      (node (ref "U1") (pin "69") (pinfunction "PDAT15_69") (pintype "output"))
    )
    (net (code "80") (name "Net-(U1-XI)") (class "Default")
      (node (ref "C2") (pin "2") (pinfunction "2_2") (pintype "passive"))
      (node (ref "R3") (pin "2") (pinfunction "2_2") (pintype "passive"))
      (node (ref "U1") (pin "3") (pinfunction "XI_3") (pintype "input"))
      (node (ref "Y1") (pin "2") (pinfunction "2_2") (pintype "passive"))
    )
    (net (code "81") (name "Net-(U1-XO)") (class "Default")
      (node (ref "C3") (pin "2") (pinfunction "2_2") (pintype "passive"))
      (node (ref "R3") (pin "1") (pinfunction "1_1") (pintype "passive"))
      (node (ref "U1") (pin "4") (pinfunction "XO_4") (pintype "output"))
      (node (ref "Y1") (pin "1") (pinfunction "1_1") (pintype "passive"))
    )
    (net (code "82") (name "Net-(U3-SHDN)") (class "Default")
      (node (ref "D3") (pin "A") (pinfunction "A_A") (pintype "passive"))
      (node (ref "D4") (pin "A") (pinfunction "A_A") (pintype "passive"))
      (node (ref "R11") (pin "1") (pinfunction "1_1") (pintype "passive"))
      (node (ref "U3") (pin "4") (pinfunction "SHDN_4") (pintype "bidirectional"))
    )
    (net (code "83") (name "VIN") (class "Default")
      (node (ref "C16") (pin "1") (pinfunction "1_1") (pintype "passive"))
      (node (ref "FB2") (pin "2") (pinfunction "P$2_2") (pintype "passive"))
      (node (ref "JP1") (pin "15") (pinfunction "15_15") (pintype "passive"))
      (node (ref "L1") (pin "P$1") (pinfunction "1_P$1") (pintype "passive"))
      (node (ref "R11") (pin "2") (pinfunction "2_2") (pintype "passive"))
      (node (ref "U3") (pin "5") (pinfunction "VIN_5") (pintype "bidirectional"))
    )
    (net (code "84") (name "unconnected-(J1AC-MS-Pad35)") (class "Default")
      (node (ref "J1") (pin "35") (pinfunction "MS_35") (pintype "passive"))
    )
    (net (code "85") (name "unconnected-(U1-DB0-Pad82)") (class "Default")
      (node (ref "U1") (pin "82") (pinfunction "DB0_82") (pintype "bidirectional"))
    )
    (net (code "86") (name "unconnected-(U1-DB1-Pad83)") (class "Default")
      (node (ref "U1") (pin "83") (pinfunction "DB1_83") (pintype "bidirectional"))
    )
    (net (code "87") (name "unconnected-(U1-DB2-Pad84)") (class "Default")
      (node (ref "U1") (pin "84") (pinfunction "DB2_84") (pintype "bidirectional"))
    )
    (net (code "88") (name "unconnected-(U1-DB3-Pad88)") (class "Default")
      (node (ref "U1") (pin "88") (pinfunction "DB3_88") (pintype "bidirectional"))
    )
    (net (code "89") (name "unconnected-(U1-DB4-Pad89)") (class "Default")
      (node (ref "U1") (pin "89") (pinfunction "DB4_89") (pintype "bidirectional"))
    )
    (net (code "90") (name "unconnected-(U1-DB5-Pad90)") (class "Default")
      (node (ref "U1") (pin "90") (pinfunction "DB5_90") (pintype "bidirectional"))
    )
    (net (code "91") (name "unconnected-(U1-DB6-Pad91)") (class "Default")
      (node (ref "U1") (pin "91") (pinfunction "DB6_91") (pintype "bidirectional"))
    )
    (net (code "92") (name "unconnected-(U1-DB7-Pad92)") (class "Default")
      (node (ref "U1") (pin "92") (pinfunction "DB7_92") (pintype "bidirectional"))
    )
    (net (code "93") (name "unconnected-(U1-DB8-Pad93)") (class "Default")
      (node (ref "U1") (pin "93") (pinfunction "DB8_93") (pintype "bidirectional"))
    )
    (net (code "94") (name "unconnected-(U1-DB9-Pad94)") (class "Default")
      (node (ref "U1") (pin "94") (pinfunction "DB9_94") (pintype "bidirectional"))
    )
    (net (code "95") (name "unconnected-(U1-DB10-Pad95)") (class "Default")
      (node (ref "U1") (pin "95") (pinfunction "DB10_95") (pintype "bidirectional"))
    )
    (net (code "96") (name "unconnected-(U1-DB11-Pad96)") (class "Default")
      (node (ref "U1") (pin "96") (pinfunction "DB11_96") (pintype "bidirectional"))
    )
    (net (code "97") (name "unconnected-(U1-DB12-Pad97)") (class "Default")
      (node (ref "U1") (pin "97") (pinfunction "DB12_97") (pintype "bidirectional"))
    )
    (net (code "98") (name "unconnected-(U1-DB13-Pad98)") (class "Default")
      (node (ref "U1") (pin "98") (pinfunction "DB13_98") (pintype "bidirectional"))
    )
    (net (code "99") (name "unconnected-(U1-DB14-Pad99)") (class "Default")
      (node (ref "U1") (pin "99") (pinfunction "DB14_99") (pintype "bidirectional"))
    )
    (net (code "100") (name "unconnected-(U1-DB15-Pad100)") (class "Default")
      (node (ref "U1") (pin "100") (pinfunction "DB15_100") (pintype "bidirectional"))
    )
    (net (code "101") (name "unconnected-(U1-KOUT0{slash}GPO0-Pad32)") (class "Default")
      (node (ref "U1") (pin "32") (pinfunction "KOUT0/GPO0_32") (pintype "output"))
    )
    (net (code "102") (name "unconnected-(U1-KOUT1{slash}GPO1-Pad31)") (class "Default")
      (node (ref "U1") (pin "31") (pinfunction "KOUT1/GPO1_31") (pintype "output"))
    )
    (net (code "103") (name "unconnected-(U1-KOUT2{slash}GPO2-Pad30)") (class "Default")
      (node (ref "U1") (pin "30") (pinfunction "KOUT2/GPO2_30") (pintype "output"))
    )
    (net (code "104") (name "unconnected-(U1-KOUT3{slash}GPO3-Pad29)") (class "Default")
      (node (ref "U1") (pin "29") (pinfunction "KOUT3/GPO3_29") (pintype "output"))
    )
    (net (code "105") (name "unconnected-(U1-PWM2-Pad15)") (class "Default")
      (node (ref "U1") (pin "15") (pinfunction "PWM2_15") (pintype "output"))
    )
    (net (code "106") (name "unconnected-(U1-SFCL-Pad18)") (class "Default")
      (node (ref "U1") (pin "18") (pinfunction "SFCL_18") (pintype "output"))
    )
    (net (code "107") (name "unconnected-(U1-SFCS0#-Pad21)") (class "Default")
      (node (ref "U1") (pin "21") (pinfunction "SFCS0#_21") (pintype "output"))
    )
    (net (code "108") (name "unconnected-(U1-SFCS1#-Pad22)") (class "Default")
      (node (ref "U1") (pin "22") (pinfunction "SFCS1#_22") (pintype "output"))
    )
    (net (code "109") (name "unconnected-(U1-SFDI-Pad19)") (class "Default")
      (node (ref "U1") (pin "19") (pinfunction "SFDI_19") (pintype "bidirectional"))
    )
    (net (code "110") (name "unconnected-(U1-SFDO-Pad20)") (class "Default")
      (node (ref "U1") (pin "20") (pinfunction "SFDO_20") (pintype "bidirectional"))
    )
    (net (code "111") (name "unconnected-(U4-P4-Pad4)") (class "Default")
      (node (ref "U4") (pin "4") (pinfunction "P4_4") (pintype "bidirectional"))
    )
    (net (code "112") (name "unconnected-(U5-5A-Pad11)") (class "Default")
      (node (ref "U5") (pin "11") (pinfunction "5A_11") (pintype "bidirectional"))
    )
    (net (code "113") (name "unconnected-(U5-5Y-Pad12)") (class "Default")
      (node (ref "U5") (pin "12") (pinfunction "5Y_12") (pintype "bidirectional"))
    )
    (net (code "114") (name "unconnected-(U5-6A-Pad14)") (class "Default")
      (node (ref "U5") (pin "14") (pinfunction "6A_14") (pintype "bidirectional"))
    )
    (net (code "115") (name "unconnected-(U5-6Y-Pad15)") (class "Default")
      (node (ref "U5") (pin "15") (pinfunction "6Y_15") (pintype "bidirectional"))
    )
  )
)
